# SolarSimulatorPanel.net
KiCad netlist of a schematic drawn in EAGLE
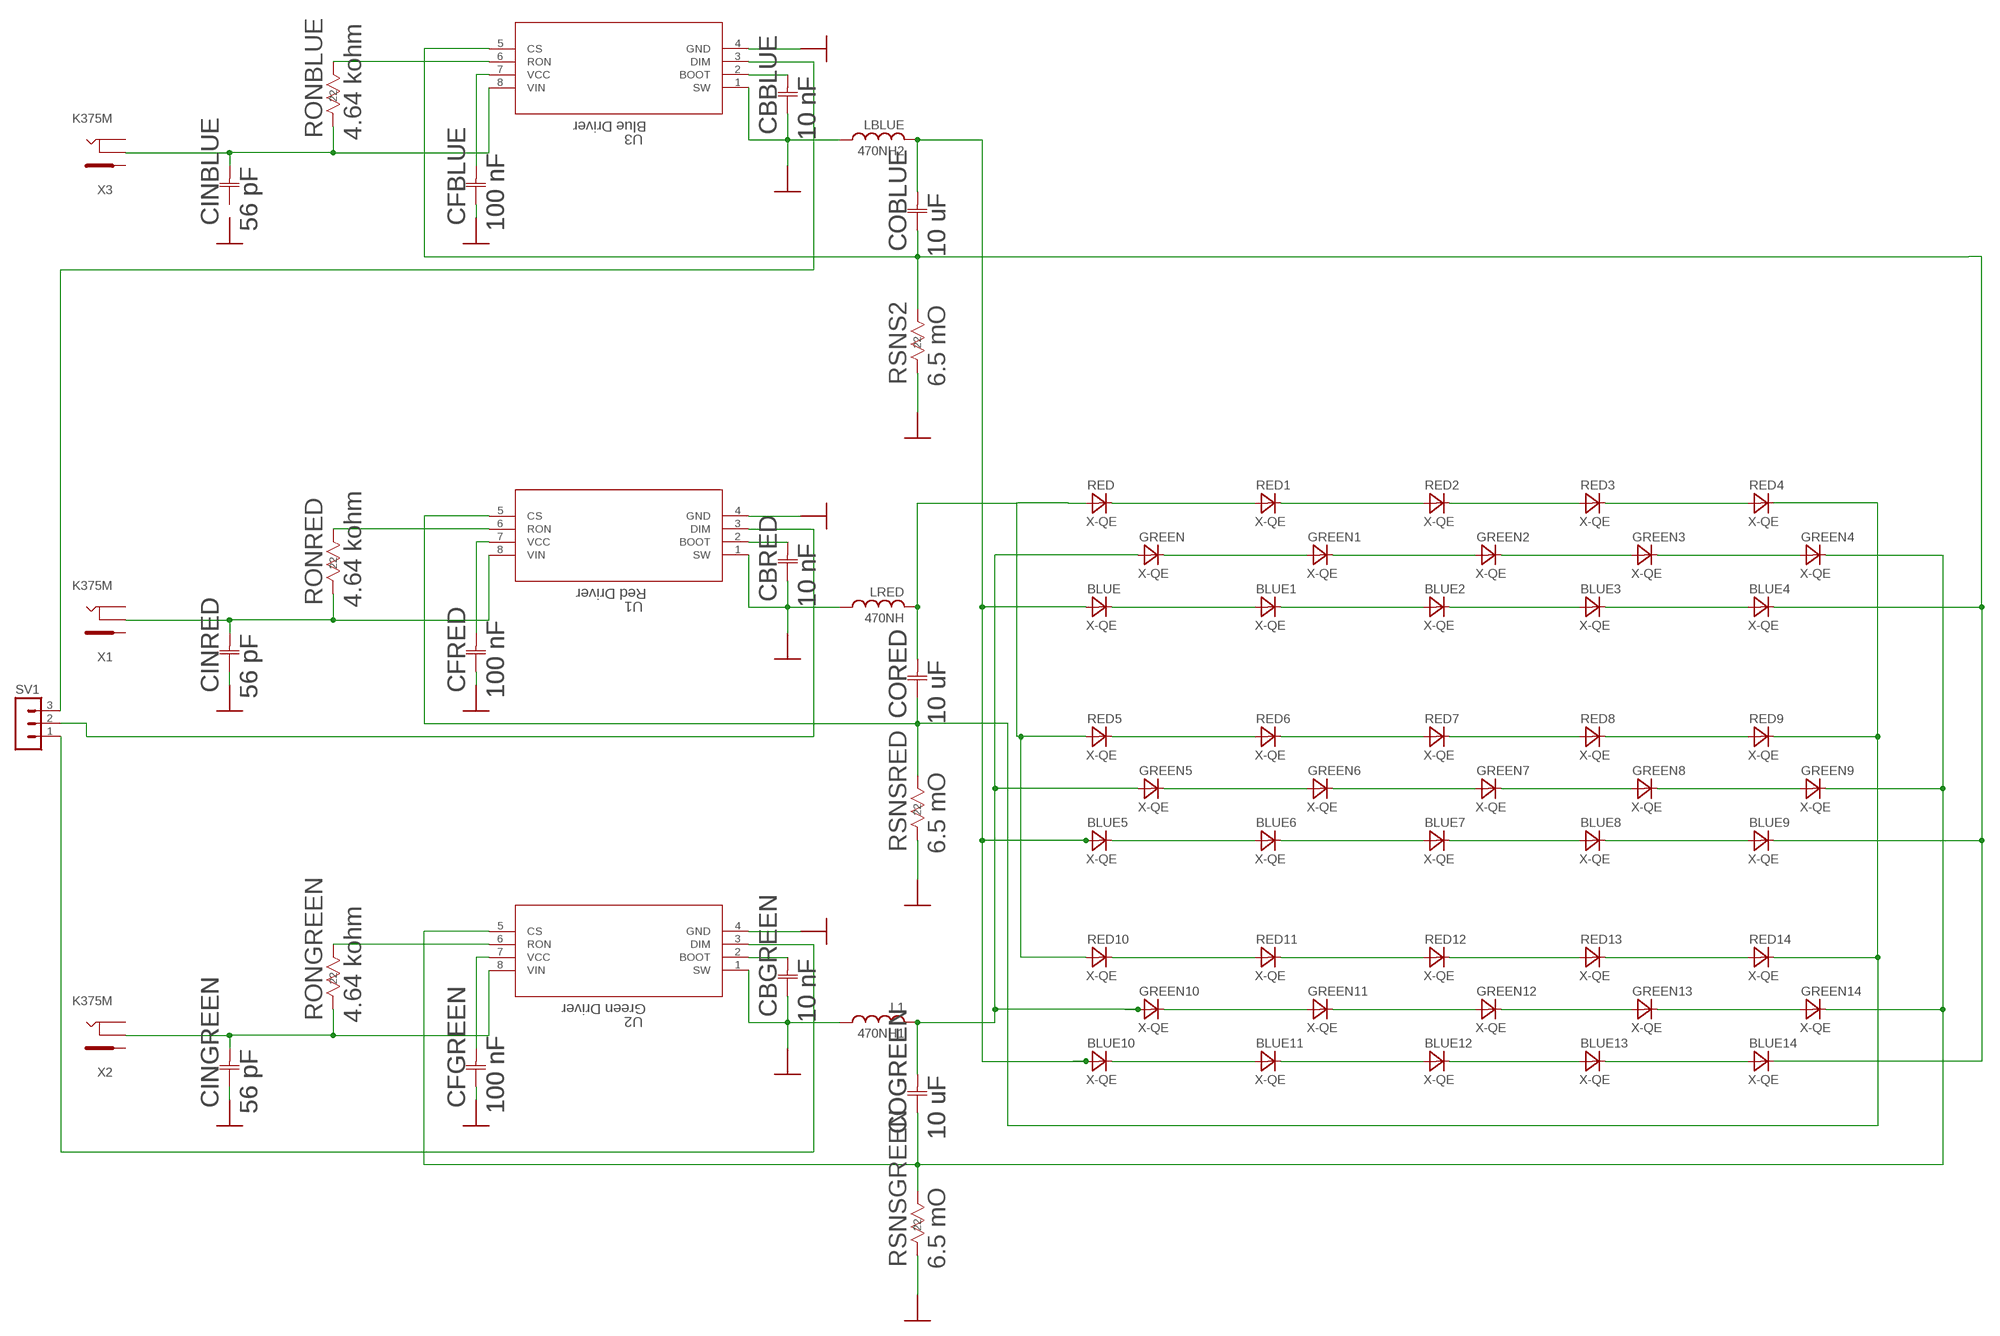
[diagram p0: schematic, sheet 1]

(export (version "E")
  (design (tool "Eeschema 10.0.6"))
  (components
    (comp (ref "470NH")
      (value "LRED")
      (footprint "eagle-import:CAPC2012X135N")
      (libsource (lib "eagle-import") (part "LQM21INDUCTOR"))
    )
    (comp (ref "470NH1")
      (value "L1")
      (footprint "eagle-import:CAPC2012X135N")
      (libsource (lib "eagle-import") (part "LQM21INDUCTOR"))
    )
    (comp (ref "470NH2")
      (value "LBLUE")
      (footprint "eagle-import:CAPC2012X135N")
      (libsource (lib "eagle-import") (part "LQM21INDUCTOR"))
    )
    (comp (ref "BLUE")
      (value "X-QE")
      (footprint "eagle-import:X-QE")
      (libsource (lib "eagle-import") (part "X-QE"))
    )
    (comp (ref "BLUE1")
      (value "X-QE")
      (footprint "eagle-import:X-QE")
      (libsource (lib "eagle-import") (part "X-QE"))
    )
    (comp (ref "BLUE2")
      (value "X-QE")
      (footprint "eagle-import:X-QE")
      (libsource (lib "eagle-import") (part "X-QE"))
    )
    (comp (ref "BLUE3")
      (value "X-QE")
      (footprint "eagle-import:X-QE")
      (libsource (lib "eagle-import") (part "X-QE"))
    )
    (comp (ref "BLUE4")
      (value "X-QE")
      (footprint "eagle-import:X-QE")
      (libsource (lib "eagle-import") (part "X-QE"))
    )
    (comp (ref "BLUE5")
      (value "X-QE")
      (footprint "eagle-import:X-QE")
      (libsource (lib "eagle-import") (part "X-QE"))
    )
    (comp (ref "BLUE6")
      (value "X-QE")
      (footprint "eagle-import:X-QE")
      (libsource (lib "eagle-import") (part "X-QE"))
    )
    (comp (ref "BLUE7")
      (value "X-QE")
      (footprint "eagle-import:X-QE")
      (libsource (lib "eagle-import") (part "X-QE"))
    )
    (comp (ref "BLUE8")
      (value "X-QE")
      (footprint "eagle-import:X-QE")
      (libsource (lib "eagle-import") (part "X-QE"))
    )
    (comp (ref "BLUE9")
      (value "X-QE")
      (footprint "eagle-import:X-QE")
      (libsource (lib "eagle-import") (part "X-QE"))
    )
    (comp (ref "BLUE10")
      (value "X-QE")
      (footprint "eagle-import:X-QE")
      (libsource (lib "eagle-import") (part "X-QE"))
    )
    (comp (ref "BLUE11")
      (value "X-QE")
      (footprint "eagle-import:X-QE")
      (libsource (lib "eagle-import") (part "X-QE"))
    )
    (comp (ref "BLUE12")
      (value "X-QE")
      (footprint "eagle-import:X-QE")
      (libsource (lib "eagle-import") (part "X-QE"))
    )
    (comp (ref "BLUE13")
      (value "X-QE")
      (footprint "eagle-import:X-QE")
      (libsource (lib "eagle-import") (part "X-QE"))
    )
    (comp (ref "BLUE14")
      (value "X-QE")
      (footprint "eagle-import:X-QE")
      (libsource (lib "eagle-import") (part "X-QE"))
    )
    (comp (ref "CBBLUE")
      (value "10 nF")
      (footprint "eagle-import:C1206K")
      (libsource (lib "eagle-import") (part "CB"))
    )
    (comp (ref "CBGREEN")
      (value "10 nF")
      (footprint "eagle-import:C1206K")
      (libsource (lib "eagle-import") (part "CB"))
    )
    (comp (ref "CBRED")
      (value "10 nF")
      (footprint "eagle-import:C1206K")
      (libsource (lib "eagle-import") (part "CB"))
    )
    (comp (ref "CFBLUE")
      (value "100 nF")
      (footprint "eagle-import:C1206")
      (libsource (lib "eagle-import") (part "CFCF"))
    )
    (comp (ref "CFGREEN")
      (value "100 nF")
      (footprint "eagle-import:C1206")
      (libsource (lib "eagle-import") (part "CFCF"))
    )
    (comp (ref "CFRED")
      (value "100 nF")
      (footprint "eagle-import:C1206")
      (libsource (lib "eagle-import") (part "CFCF"))
    )
    (comp (ref "CINBLUE")
      (value "56 pF")
      (footprint "eagle-import:CAP_0603G")
      (fields (field (name "MANUFACTURER_PART_NUMBER") "06031A560GAT2A"))
      (libsource (lib "eagle-import") (part "INPUTCAPACITOR"))
    )
    (comp (ref "CINGREEN")
      (value "56 pF")
      (footprint "eagle-import:CAP_0603G")
      (fields (field (name "MANUFACTURER_PART_NUMBER") "06031A560GAT2A"))
      (libsource (lib "eagle-import") (part "INPUTCAPACITOR"))
    )
    (comp (ref "CINRED")
      (value "56 pF")
      (footprint "eagle-import:CAP_0603G")
      (fields (field (name "MANUFACTURER_PART_NUMBER") "06031A560GAT2A"))
      (libsource (lib "eagle-import") (part "INPUTCAPACITOR"))
    )
    (comp (ref "COBLUE")
      (value "10 uF")
      (footprint "eagle-import:CAP_3225")
      (fields (field (name "MANUFACTURER_PART_NUMBER") "C3225X7R1H106M250AC"))
      (libsource (lib "eagle-import") (part "OUTPUTCAPACITOR"))
    )
    (comp (ref "COGREEN")
      (value "10 uF")
      (footprint "eagle-import:CAP_3225")
      (fields (field (name "MANUFACTURER_PART_NUMBER") "C3225X7R1H106M250AC"))
      (libsource (lib "eagle-import") (part "OUTPUTCAPACITOR"))
    )
    (comp (ref "CORED")
      (value "10 uF")
      (footprint "eagle-import:CAP_3225")
      (fields (field (name "MANUFACTURER_PART_NUMBER") "C3225X7R1H106M250AC"))
      (libsource (lib "eagle-import") (part "OUTPUTCAPACITOR"))
    )
    (comp (ref "GREEN")
      (value "X-QE")
      (footprint "eagle-import:X-QE")
      (libsource (lib "eagle-import") (part "X-QE"))
    )
    (comp (ref "GREEN1")
      (value "X-QE")
      (footprint "eagle-import:X-QE")
      (libsource (lib "eagle-import") (part "X-QE"))
    )
    (comp (ref "GREEN2")
      (value "X-QE")
      (footprint "eagle-import:X-QE")
      (libsource (lib "eagle-import") (part "X-QE"))
    )
    (comp (ref "GREEN3")
      (value "X-QE")
      (footprint "eagle-import:X-QE")
      (libsource (lib "eagle-import") (part "X-QE"))
    )
    (comp (ref "GREEN4")
      (value "X-QE")
      (footprint "eagle-import:X-QE")
      (libsource (lib "eagle-import") (part "X-QE"))
    )
    (comp (ref "GREEN5")
      (value "X-QE")
      (footprint "eagle-import:X-QE")
      (libsource (lib "eagle-import") (part "X-QE"))
    )
    (comp (ref "GREEN6")
      (value "X-QE")
      (footprint "eagle-import:X-QE")
      (libsource (lib "eagle-import") (part "X-QE"))
    )
    (comp (ref "GREEN7")
      (value "X-QE")
      (footprint "eagle-import:X-QE")
      (libsource (lib "eagle-import") (part "X-QE"))
    )
    (comp (ref "GREEN8")
      (value "X-QE")
      (footprint "eagle-import:X-QE")
      (libsource (lib "eagle-import") (part "X-QE"))
    )
    (comp (ref "GREEN9")
      (value "X-QE")
      (footprint "eagle-import:X-QE")
      (libsource (lib "eagle-import") (part "X-QE"))
    )
    (comp (ref "GREEN10")
      (value "X-QE")
      (footprint "eagle-import:X-QE")
      (libsource (lib "eagle-import") (part "X-QE"))
    )
    (comp (ref "GREEN11")
      (value "X-QE")
      (footprint "eagle-import:X-QE")
      (libsource (lib "eagle-import") (part "X-QE"))
    )
    (comp (ref "GREEN12")
      (value "X-QE")
      (footprint "eagle-import:X-QE")
      (libsource (lib "eagle-import") (part "X-QE"))
    )
    (comp (ref "GREEN13")
      (value "X-QE")
      (footprint "eagle-import:X-QE")
      (libsource (lib "eagle-import") (part "X-QE"))
    )
    (comp (ref "GREEN14")
      (value "X-QE")
      (footprint "eagle-import:X-QE")
      (libsource (lib "eagle-import") (part "X-QE"))
    )
    (comp (ref "RED")
      (value "X-QE")
      (footprint "eagle-import:X-QE")
      (libsource (lib "eagle-import") (part "X-QE"))
    )
    (comp (ref "RED1")
      (value "X-QE")
      (footprint "eagle-import:X-QE")
      (libsource (lib "eagle-import") (part "X-QE"))
    )
    (comp (ref "RED2")
      (value "X-QE")
      (footprint "eagle-import:X-QE")
      (libsource (lib "eagle-import") (part "X-QE"))
    )
    (comp (ref "RED3")
      (value "X-QE")
      (footprint "eagle-import:X-QE")
      (libsource (lib "eagle-import") (part "X-QE"))
    )
    (comp (ref "RED4")
      (value "X-QE")
      (footprint "eagle-import:X-QE")
      (libsource (lib "eagle-import") (part "X-QE"))
    )
    (comp (ref "RED5")
      (value "X-QE")
      (footprint "eagle-import:X-QE")
      (libsource (lib "eagle-import") (part "X-QE"))
    )
    (comp (ref "RED6")
      (value "X-QE")
      (footprint "eagle-import:X-QE")
      (libsource (lib "eagle-import") (part "X-QE"))
    )
    (comp (ref "RED7")
      (value "X-QE")
      (footprint "eagle-import:X-QE")
      (libsource (lib "eagle-import") (part "X-QE"))
    )
    (comp (ref "RED8")
      (value "X-QE")
      (footprint "eagle-import:X-QE")
      (libsource (lib "eagle-import") (part "X-QE"))
    )
    (comp (ref "RED9")
      (value "X-QE")
      (footprint "eagle-import:X-QE")
      (libsource (lib "eagle-import") (part "X-QE"))
    )
    (comp (ref "RED10")
      (value "X-QE")
      (footprint "eagle-import:X-QE")
      (libsource (lib "eagle-import") (part "X-QE"))
    )
    (comp (ref "RED11")
      (value "X-QE")
      (footprint "eagle-import:X-QE")
      (libsource (lib "eagle-import") (part "X-QE"))
    )
    (comp (ref "RED12")
      (value "X-QE")
      (footprint "eagle-import:X-QE")
      (libsource (lib "eagle-import") (part "X-QE"))
    )
    (comp (ref "RED13")
      (value "X-QE")
      (footprint "eagle-import:X-QE")
      (libsource (lib "eagle-import") (part "X-QE"))
    )
    (comp (ref "RED14")
      (value "X-QE")
      (footprint "eagle-import:X-QE")
      (libsource (lib "eagle-import") (part "X-QE"))
    )
    (comp (ref "RONBLUE")
      (value "4.64 kohm")
      (footprint "eagle-import:RC0603N")
      (fields (field (name "MANUFACTURER_PART_NUMBER") "RT0603BRD074K64L"))
      (libsource (lib "eagle-import") (part "RT0603BRD074K64L"))
    )
    (comp (ref "RONGREEN")
      (value "4.64 kohm")
      (footprint "eagle-import:RC0603N")
      (fields (field (name "MANUFACTURER_PART_NUMBER") "RT0603BRD074K64L"))
      (libsource (lib "eagle-import") (part "RT0603BRD074K64L"))
    )
    (comp (ref "RONRED")
      (value "4.64 kohm")
      (footprint "eagle-import:RC0603N")
      (fields (field (name "MANUFACTURER_PART_NUMBER") "RT0603BRD074K64L"))
      (libsource (lib "eagle-import") (part "RT0603BRD074K64L"))
    )
    (comp (ref "RSNS2")
      (value "6.5 mO")
      (footprint "eagle-import:R2512")
      (libsource (lib "eagle-import") (part "RSNS"))
    )
    (comp (ref "RSNSGREEN")
      (value "6.5 mO")
      (footprint "eagle-import:R2512")
      (libsource (lib "eagle-import") (part "RSNS"))
    )
    (comp (ref "RSNSRED")
      (value "6.5 mO")
      (footprint "eagle-import:R2512")
      (libsource (lib "eagle-import") (part "RSNS"))
    )
    (comp (ref "SV1")
      (value "MA03-1")
      (footprint "eagle-import:MA03-1")
      (libsource (lib "eagle-import") (part "MA03-1"))
    )
    (comp (ref "U1")
      (value "Red Driver")
      (footprint "eagle-import:M08A")
      (fields (field (name "MANUFACTURER_PART_NUMBER") "lm3404hvma"))
      (libsource (lib "eagle-import") (part "LM3404HVMA"))
    )
    (comp (ref "U2")
      (value "Green Driver")
      (footprint "eagle-import:M08A")
      (fields (field (name "MANUFACTURER_PART_NUMBER") "lm3404hvma"))
      (libsource (lib "eagle-import") (part "LM3404HVMA"))
    )
    (comp (ref "U3")
      (value "Blue Driver")
      (footprint "eagle-import:M08A")
      (fields (field (name "MANUFACTURER_PART_NUMBER") "lm3404hvma"))
      (libsource (lib "eagle-import") (part "LM3404HVMA"))
    )
    (comp (ref "X1")
      (value "K375M")
      (footprint "eagle-import:K375M")
      (libsource (lib "eagle-import") (part "K375M"))
    )
    (comp (ref "X2")
      (value "K375M")
      (footprint "eagle-import:K375M")
      (libsource (lib "eagle-import") (part "K375M"))
    )
    (comp (ref "X3")
      (value "K375M")
      (footprint "eagle-import:K375M")
      (libsource (lib "eagle-import") (part "K375M"))
    )
  )
  (nets
    (net (code "1") (name "Net-(BLUE-A)") (class "Default")
      (node (ref "470NH2") (pin "2") (pinfunction "2_2") (pintype "passive"))
      (node (ref "BLUE") (pin "INPUT") (pinfunction "A_INPUT") (pintype "passive"))
      (node (ref "BLUE10") (pin "INPUT") (pinfunction "A_INPUT") (pintype "passive"))
      (node (ref "BLUE5") (pin "INPUT") (pinfunction "A_INPUT") (pintype "passive"))
      (node (ref "COBLUE") (pin "2") (pinfunction "22_2") (pintype "passive"))
    )
    (net (code "2") (name "Net-(BLUE-C)") (class "Default")
      (node (ref "BLUE") (pin "OUTPUT") (pinfunction "C_OUTPUT") (pintype "passive"))
      (node (ref "BLUE1") (pin "INPUT") (pinfunction "A_INPUT") (pintype "passive"))
    )
    (net (code "3") (name "Net-(BLUE1-C)") (class "Default")
      (node (ref "BLUE1") (pin "OUTPUT") (pinfunction "C_OUTPUT") (pintype "passive"))
      (node (ref "BLUE2") (pin "INPUT") (pinfunction "A_INPUT") (pintype "passive"))
    )
    (net (code "4") (name "Net-(BLUE2-C)") (class "Default")
      (node (ref "BLUE2") (pin "OUTPUT") (pinfunction "C_OUTPUT") (pintype "passive"))
      (node (ref "BLUE3") (pin "INPUT") (pinfunction "A_INPUT") (pintype "passive"))
    )
    (net (code "5") (name "Net-(BLUE3-C)") (class "Default")
      (node (ref "BLUE3") (pin "OUTPUT") (pinfunction "C_OUTPUT") (pintype "passive"))
      (node (ref "BLUE4") (pin "INPUT") (pinfunction "A_INPUT") (pintype "passive"))
    )
    (net (code "6") (name "Net-(BLUE5-C)") (class "Default")
      (node (ref "BLUE5") (pin "OUTPUT") (pinfunction "C_OUTPUT") (pintype "passive"))
      (node (ref "BLUE6") (pin "INPUT") (pinfunction "A_INPUT") (pintype "passive"))
    )
    (net (code "7") (name "Net-(BLUE6-C)") (class "Default")
      (node (ref "BLUE6") (pin "OUTPUT") (pinfunction "C_OUTPUT") (pintype "passive"))
      (node (ref "BLUE7") (pin "INPUT") (pinfunction "A_INPUT") (pintype "passive"))
    )
    (net (code "8") (name "Net-(BLUE7-C)") (class "Default")
      (node (ref "BLUE7") (pin "OUTPUT") (pinfunction "C_OUTPUT") (pintype "passive"))
      (node (ref "BLUE8") (pin "INPUT") (pinfunction "A_INPUT") (pintype "passive"))
    )
    (net (code "9") (name "Net-(BLUE8-C)") (class "Default")
      (node (ref "BLUE8") (pin "OUTPUT") (pinfunction "C_OUTPUT") (pintype "passive"))
      (node (ref "BLUE9") (pin "INPUT") (pinfunction "A_INPUT") (pintype "passive"))
    )
    (net (code "10") (name "Net-(BLUE10-C)") (class "Default")
      (node (ref "BLUE10") (pin "OUTPUT") (pinfunction "C_OUTPUT") (pintype "passive"))
      (node (ref "BLUE11") (pin "INPUT") (pinfunction "A_INPUT") (pintype "passive"))
    )
    (net (code "11") (name "Net-(BLUE11-C)") (class "Default")
      (node (ref "BLUE11") (pin "OUTPUT") (pinfunction "C_OUTPUT") (pintype "passive"))
      (node (ref "BLUE12") (pin "INPUT") (pinfunction "A_INPUT") (pintype "passive"))
    )
    (net (code "12") (name "Net-(BLUE12-C)") (class "Default")
      (node (ref "BLUE12") (pin "OUTPUT") (pinfunction "C_OUTPUT") (pintype "passive"))
      (node (ref "BLUE13") (pin "INPUT") (pinfunction "A_INPUT") (pintype "passive"))
    )
    (net (code "13") (name "Net-(BLUE13-C)") (class "Default")
      (node (ref "BLUE13") (pin "OUTPUT") (pinfunction "C_OUTPUT") (pintype "passive"))
      (node (ref "BLUE14") (pin "INPUT") (pinfunction "A_INPUT") (pintype "passive"))
    )
    (net (code "14") (name "Net-(BLUE14-C)") (class "Default")
      (node (ref "BLUE14") (pin "OUTPUT") (pinfunction "C_OUTPUT") (pintype "passive"))
      (node (ref "BLUE4") (pin "OUTPUT") (pinfunction "C_OUTPUT") (pintype "passive"))
      (node (ref "BLUE9") (pin "OUTPUT") (pinfunction "C_OUTPUT") (pintype "passive"))
      (node (ref "COBLUE") (pin "1") (pinfunction "11_1") (pintype "passive"))
      (node (ref "RSNS2") (pin "1") (pinfunction "11_1") (pintype "passive"))
      (node (ref "U3") (pin "5") (pinfunction "CS_5") (pintype "input"))
    )
    (net (code "15") (name "Net-(CBBLUE-11)") (class "Default")
      (node (ref "470NH2") (pin "1") (pinfunction "1_1") (pintype "passive"))
      (node (ref "CBBLUE") (pin "1") (pinfunction "11_1") (pintype "passive"))
      (node (ref "U3") (pin "1") (pinfunction "SW_1") (pintype "power_in"))
    )
    (net (code "16") (name "Net-(CBBLUE-22)") (class "Default")
      (node (ref "CBBLUE") (pin "2") (pinfunction "22_2") (pintype "passive"))
      (node (ref "U3") (pin "2") (pinfunction "BOOT_2") (pintype "input"))
    )
    (net (code "17") (name "Net-(CBGREEN-11)") (class "Default")
      (node (ref "470NH1") (pin "1") (pinfunction "1_1") (pintype "passive"))
      (node (ref "CBGREEN") (pin "1") (pinfunction "11_1") (pintype "passive"))
      (node (ref "U2") (pin "1") (pinfunction "SW_1") (pintype "power_in"))
    )
    (net (code "18") (name "Net-(CBGREEN-22)") (class "Default")
      (node (ref "CBGREEN") (pin "2") (pinfunction "22_2") (pintype "passive"))
      (node (ref "U2") (pin "2") (pinfunction "BOOT_2") (pintype "input"))
    )
    (net (code "19") (name "Net-(CBRED-11)") (class "Default")
      (node (ref "470NH") (pin "1") (pinfunction "1_1") (pintype "passive"))
      (node (ref "CBRED") (pin "1") (pinfunction "11_1") (pintype "passive"))
      (node (ref "U1") (pin "1") (pinfunction "SW_1") (pintype "power_in"))
    )
    (net (code "20") (name "Net-(CBRED-22)") (class "Default")
      (node (ref "CBRED") (pin "2") (pinfunction "22_2") (pintype "passive"))
      (node (ref "U1") (pin "2") (pinfunction "BOOT_2") (pintype "input"))
    )
    (net (code "21") (name "Net-(CFBLUE-22)") (class "Default")
      (node (ref "CFBLUE") (pin "2") (pinfunction "22_2") (pintype "passive"))
      (node (ref "U3") (pin "7") (pinfunction "VCC_7") (pintype "power_in"))
    )
    (net (code "22") (name "Net-(CFGREEN-22)") (class "Default")
      (node (ref "CFGREEN") (pin "2") (pinfunction "22_2") (pintype "passive"))
      (node (ref "U2") (pin "7") (pinfunction "VCC_7") (pintype "power_in"))
    )
    (net (code "23") (name "Net-(CFRED-22)") (class "Default")
      (node (ref "CFRED") (pin "2") (pinfunction "22_2") (pintype "passive"))
      (node (ref "U1") (pin "7") (pinfunction "VCC_7") (pintype "power_in"))
    )
    (net (code "24") (name "Net-(CINBLUE-22)") (class "Default")
      (node (ref "CINBLUE") (pin "2") (pinfunction "22_2") (pintype "passive"))
      (node (ref "RONBLUE") (pin "2") (pinfunction "22_2") (pintype "passive"))
      (node (ref "U3") (pin "8") (pinfunction "VIN_8") (pintype "power_in"))
      (node (ref "X3") (pin "3") (pinfunction "3_3") (pintype "passive"))
    )
    (net (code "25") (name "Net-(CINGREEN-22)") (class "Default")
      (node (ref "CINGREEN") (pin "2") (pinfunction "22_2") (pintype "passive"))
      (node (ref "RONGREEN") (pin "2") (pinfunction "22_2") (pintype "passive"))
      (node (ref "U2") (pin "8") (pinfunction "VIN_8") (pintype "power_in"))
      (node (ref "X2") (pin "3") (pinfunction "3_3") (pintype "passive"))
    )
    (net (code "26") (name "Net-(CINRED-22)") (class "Default")
      (node (ref "CINRED") (pin "2") (pinfunction "22_2") (pintype "passive"))
      (node (ref "RONRED") (pin "2") (pinfunction "22_2") (pintype "passive"))
      (node (ref "U1") (pin "8") (pinfunction "VIN_8") (pintype "power_in"))
      (node (ref "X1") (pin "3") (pinfunction "3_3") (pintype "passive"))
    )
    (net (code "27") (name "Net-(COGREEN-11)") (class "Default")
      (node (ref "COGREEN") (pin "1") (pinfunction "11_1") (pintype "passive"))
      (node (ref "GREEN14") (pin "OUTPUT") (pinfunction "C_OUTPUT") (pintype "passive"))
      (node (ref "GREEN4") (pin "OUTPUT") (pinfunction "C_OUTPUT") (pintype "passive"))
      (node (ref "GREEN9") (pin "OUTPUT") (pinfunction "C_OUTPUT") (pintype "passive"))
      (node (ref "RSNSGREEN") (pin "1") (pinfunction "11_1") (pintype "passive"))
      (node (ref "U2") (pin "5") (pinfunction "CS_5") (pintype "input"))
    )
    (net (code "28") (name "Net-(COGREEN-22)") (class "Default")
      (node (ref "470NH1") (pin "2") (pinfunction "2_2") (pintype "passive"))
      (node (ref "COGREEN") (pin "2") (pinfunction "22_2") (pintype "passive"))
      (node (ref "GREEN") (pin "INPUT") (pinfunction "A_INPUT") (pintype "passive"))
      (node (ref "GREEN10") (pin "INPUT") (pinfunction "A_INPUT") (pintype "passive"))
    )
    (net (code "29") (name "Net-(CORED-11)") (class "Default")
      (node (ref "CORED") (pin "1") (pinfunction "11_1") (pintype "passive"))
      (node (ref "RED14") (pin "OUTPUT") (pinfunction "C_OUTPUT") (pintype "passive"))
      (node (ref "RED4") (pin "OUTPUT") (pinfunction "C_OUTPUT") (pintype "passive"))
      (node (ref "RED9") (pin "OUTPUT") (pinfunction "C_OUTPUT") (pintype "passive"))
      (node (ref "RSNSRED") (pin "1") (pinfunction "11_1") (pintype "passive"))
      (node (ref "U1") (pin "5") (pinfunction "CS_5") (pintype "input"))
    )
    (net (code "30") (name "Net-(CORED-22)") (class "Default")
      (node (ref "470NH") (pin "2") (pinfunction "2_2") (pintype "passive"))
      (node (ref "CORED") (pin "2") (pinfunction "22_2") (pintype "passive"))
      (node (ref "RED") (pin "INPUT") (pinfunction "A_INPUT") (pintype "passive"))
      (node (ref "RED10") (pin "INPUT") (pinfunction "A_INPUT") (pintype "passive"))
      (node (ref "RED5") (pin "INPUT") (pinfunction "A_INPUT") (pintype "passive"))
    )
    (net (code "31") (name "Net-(GREEN-C)") (class "Default")
      (node (ref "GREEN") (pin "OUTPUT") (pinfunction "C_OUTPUT") (pintype "passive"))
      (node (ref "GREEN1") (pin "INPUT") (pinfunction "A_INPUT") (pintype "passive"))
    )
    (net (code "32") (name "Net-(GREEN1-C)") (class "Default")
      (node (ref "GREEN1") (pin "OUTPUT") (pinfunction "C_OUTPUT") (pintype "passive"))
      (node (ref "GREEN2") (pin "INPUT") (pinfunction "A_INPUT") (pintype "passive"))
    )
    (net (code "33") (name "Net-(GREEN2-C)") (class "Default")
      (node (ref "GREEN2") (pin "OUTPUT") (pinfunction "C_OUTPUT") (pintype "passive"))
      (node (ref "GREEN3") (pin "INPUT") (pinfunction "A_INPUT") (pintype "passive"))
    )
    (net (code "34") (name "Net-(GREEN3-C)") (class "Default")
      (node (ref "GREEN3") (pin "OUTPUT") (pinfunction "C_OUTPUT") (pintype "passive"))
      (node (ref "GREEN4") (pin "INPUT") (pinfunction "A_INPUT") (pintype "passive"))
    )
    (net (code "35") (name "Net-(GREEN5-C)") (class "Default")
      (node (ref "GREEN5") (pin "OUTPUT") (pinfunction "C_OUTPUT") (pintype "passive"))
      (node (ref "GREEN6") (pin "INPUT") (pinfunction "A_INPUT") (pintype "passive"))
    )
    (net (code "36") (name "Net-(GREEN6-C)") (class "Default")
      (node (ref "GREEN6") (pin "OUTPUT") (pinfunction "C_OUTPUT") (pintype "passive"))
      (node (ref "GREEN7") (pin "INPUT") (pinfunction "A_INPUT") (pintype "passive"))
    )
    (net (code "37") (name "Net-(GREEN7-C)") (class "Default")
      (node (ref "GREEN7") (pin "OUTPUT") (pinfunction "C_OUTPUT") (pintype "passive"))
      (node (ref "GREEN8") (pin "INPUT") (pinfunction "A_INPUT") (pintype "passive"))
    )
    (net (code "38") (name "Net-(GREEN8-C)") (class "Default")
      (node (ref "GREEN8") (pin "OUTPUT") (pinfunction "C_OUTPUT") (pintype "passive"))
      (node (ref "GREEN9") (pin "INPUT") (pinfunction "A_INPUT") (pintype "passive"))
    )
    (net (code "39") (name "Net-(GREEN10-C)") (class "Default")
      (node (ref "GREEN10") (pin "OUTPUT") (pinfunction "C_OUTPUT") (pintype "passive"))
      (node (ref "GREEN11") (pin "INPUT") (pinfunction "A_INPUT") (pintype "passive"))
    )
    (net (code "40") (name "Net-(GREEN11-C)") (class "Default")
      (node (ref "GREEN11") (pin "OUTPUT") (pinfunction "C_OUTPUT") (pintype "passive"))
      (node (ref "GREEN12") (pin "INPUT") (pinfunction "A_INPUT") (pintype "passive"))
    )
    (net (code "41") (name "Net-(GREEN12-C)") (class "Default")
      (node (ref "GREEN12") (pin "OUTPUT") (pinfunction "C_OUTPUT") (pintype "passive"))
      (node (ref "GREEN13") (pin "INPUT") (pinfunction "A_INPUT") (pintype "passive"))
    )
    (net (code "42") (name "Net-(GREEN13-C)") (class "Default")
      (node (ref "GREEN13") (pin "OUTPUT") (pinfunction "C_OUTPUT") (pintype "passive"))
      (node (ref "GREEN14") (pin "INPUT") (pinfunction "A_INPUT") (pintype "passive"))
    )
    (net (code "43") (name "Net-(RED-C)") (class "Default")
      (node (ref "RED") (pin "OUTPUT") (pinfunction "C_OUTPUT") (pintype "passive"))
      (node (ref "RED1") (pin "INPUT") (pinfunction "A_INPUT") (pintype "passive"))
    )
    (net (code "44") (name "Net-(RED1-C)") (class "Default")
      (node (ref "RED1") (pin "OUTPUT") (pinfunction "C_OUTPUT") (pintype "passive"))
      (node (ref "RED2") (pin "INPUT") (pinfunction "A_INPUT") (pintype "passive"))
    )
    (net (code "45") (name "Net-(RED2-C)") (class "Default")
      (node (ref "RED2") (pin "OUTPUT") (pinfunction "C_OUTPUT") (pintype "passive"))
      (node (ref "RED3") (pin "INPUT") (pinfunction "A_INPUT") (pintype "passive"))
    )
    (net (code "46") (name "Net-(RED3-C)") (class "Default")
      (node (ref "RED3") (pin "OUTPUT") (pinfunction "C_OUTPUT") (pintype "passive"))
      (node (ref "RED4") (pin "INPUT") (pinfunction "A_INPUT") (pintype "passive"))
    )
    (net (code "47") (name "Net-(RED5-C)") (class "Default")
      (node (ref "RED5") (pin "OUTPUT") (pinfunction "C_OUTPUT") (pintype "passive"))
      (node (ref "RED6") (pin "INPUT") (pinfunction "A_INPUT") (pintype "passive"))
    )
    (net (code "48") (name "Net-(RED6-C)") (class "Default")
      (node (ref "RED6") (pin "OUTPUT") (pinfunction "C_OUTPUT") (pintype "passive"))
      (node (ref "RED7") (pin "INPUT") (pinfunction "A_INPUT") (pintype "passive"))
    )
    (net (code "49") (name "Net-(RED7-C)") (class "Default")
      (node (ref "RED7") (pin "OUTPUT") (pinfunction "C_OUTPUT") (pintype "passive"))
      (node (ref "RED8") (pin "INPUT") (pinfunction "A_INPUT") (pintype "passive"))
    )
    (net (code "50") (name "Net-(RED8-C)") (class "Default")
      (node (ref "RED8") (pin "OUTPUT") (pinfunction "C_OUTPUT") (pintype "passive"))
      (node (ref "RED9") (pin "INPUT") (pinfunction "A_INPUT") (pintype "passive"))
    )
    (net (code "51") (name "Net-(RED10-C)") (class "Default")
      (node (ref "RED10") (pin "OUTPUT") (pinfunction "C_OUTPUT") (pintype "passive"))
      (node (ref "RED11") (pin "INPUT") (pinfunction "A_INPUT") (pintype "passive"))
    )
    (net (code "52") (name "Net-(RED11-C)") (class "Default")
      (node (ref "RED11") (pin "OUTPUT") (pinfunction "C_OUTPUT") (pintype "passive"))
      (node (ref "RED12") (pin "INPUT") (pinfunction "A_INPUT") (pintype "passive"))
    )
    (net (code "53") (name "Net-(RED12-C)") (class "Default")
      (node (ref "RED12") (pin "OUTPUT") (pinfunction "C_OUTPUT") (pintype "passive"))
      (node (ref "RED13") (pin "INPUT") (pinfunction "A_INPUT") (pintype "passive"))
    )
    (net (code "54") (name "Net-(RED13-C)") (class "Default")
      (node (ref "RED13") (pin "OUTPUT") (pinfunction "C_OUTPUT") (pintype "passive"))
      (node (ref "RED14") (pin "INPUT") (pinfunction "A_INPUT") (pintype "passive"))
    )
    (net (code "55") (name "Net-(RONBLUE-11)") (class "Default")
      (node (ref "RONBLUE") (pin "1") (pinfunction "11_1") (pintype "passive"))
      (node (ref "U3") (pin "6") (pinfunction "RON_6") (pintype "input"))
    )
    (net (code "56") (name "Net-(RONGREEN-11)") (class "Default")
      (node (ref "RONGREEN") (pin "1") (pinfunction "11_1") (pintype "passive"))
      (node (ref "U2") (pin "6") (pinfunction "RON_6") (pintype "input"))
    )
    (net (code "57") (name "Net-(RONRED-11)") (class "Default")
      (node (ref "RONRED") (pin "1") (pinfunction "11_1") (pintype "passive"))
      (node (ref "U1") (pin "6") (pinfunction "RON_6") (pintype "input"))
    )
    (net (code "58") (name "Net-(U1-DIM)") (class "Default")
      (node (ref "SV1") (pin "2") (pinfunction "2_2") (pintype "passive"))
      (node (ref "U1") (pin "3") (pinfunction "DIM_3") (pintype "input"))
    )
    (net (code "59") (name "Net-(U2-DIM)") (class "Default")
      (node (ref "SV1") (pin "1") (pinfunction "1_1") (pintype "passive"))
      (node (ref "U2") (pin "3") (pinfunction "DIM_3") (pintype "input"))
    )
    (net (code "60") (name "Net-(U3-DIM)") (class "Default")
      (node (ref "SV1") (pin "3") (pinfunction "3_3") (pintype "passive"))
      (node (ref "U3") (pin "3") (pinfunction "DIM_3") (pintype "input"))
    )
    (net (code "61") (name "unconnected-(CFBLUE-11-Pad1)") (class "Default")
      (node (ref "CFBLUE") (pin "1") (pinfunction "11_1") (pintype "passive"))
    )
    (net (code "62") (name "unconnected-(CFGREEN-11-Pad1)") (class "Default")
      (node (ref "CFGREEN") (pin "1") (pinfunction "11_1") (pintype "passive"))
    )
    (net (code "63") (name "unconnected-(CFRED-11-Pad1)") (class "Default")
      (node (ref "CFRED") (pin "1") (pinfunction "11_1") (pintype "passive"))
    )
    (net (code "64") (name "unconnected-(CINBLUE-11-Pad1)") (class "Default")
      (node (ref "CINBLUE") (pin "1") (pinfunction "11_1") (pintype "passive"))
    )
    (net (code "65") (name "unconnected-(CINGREEN-11-Pad1)") (class "Default")
      (node (ref "CINGREEN") (pin "1") (pinfunction "11_1") (pintype "passive"))
    )
    (net (code "66") (name "unconnected-(CINRED-11-Pad1)") (class "Default")
      (node (ref "CINRED") (pin "1") (pinfunction "11_1") (pintype "passive"))
    )
    (net (code "67") (name "unconnected-(GREEN5-A-PadINPUT)") (class "Default")
      (node (ref "GREEN5") (pin "INPUT") (pinfunction "A_INPUT") (pintype "passive"))
    )
    (net (code "68") (name "unconnected-(RSNS2-22-Pad2)") (class "Default")
      (node (ref "RSNS2") (pin "2") (pinfunction "22_2") (pintype "passive"))
    )
    (net (code "69") (name "unconnected-(RSNSGREEN-22-Pad2)") (class "Default")
      (node (ref "RSNSGREEN") (pin "2") (pinfunction "22_2") (pintype "passive"))
    )
    (net (code "70") (name "unconnected-(RSNSRED-22-Pad2)") (class "Default")
      (node (ref "RSNSRED") (pin "2") (pinfunction "22_2") (pintype "passive"))
    )
    (net (code "71") (name "unconnected-(U1-GND-Pad4)") (class "Default")
      (node (ref "U1") (pin "4") (pinfunction "GND_4") (pintype "power_in"))
    )
    (net (code "72") (name "unconnected-(U2-GND-Pad4)") (class "Default")
      (node (ref "U2") (pin "4") (pinfunction "GND_4") (pintype "power_in"))
    )
    (net (code "73") (name "unconnected-(U3-GND-Pad4)") (class "Default")
      (node (ref "U3") (pin "4") (pinfunction "GND_4") (pintype "power_in"))
    )
    (net (code "74") (name "unconnected-(X1-Pad1)") (class "Default")
      (node (ref "X1") (pin "1") (pinfunction "1_1") (pintype "passive"))
    )
    (net (code "75") (name "unconnected-(X1-Pad2)") (class "Default")
      (node (ref "X1") (pin "2") (pinfunction "2_2") (pintype "passive"))
    )
    (net (code "76") (name "unconnected-(X2-Pad1)") (class "Default")
      (node (ref "X2") (pin "1") (pinfunction "1_1") (pintype "passive"))
    )
    (net (code "77") (name "unconnected-(X2-Pad2)") (class "Default")
      (node (ref "X2") (pin "2") (pinfunction "2_2") (pintype "passive"))
    )
    (net (code "78") (name "unconnected-(X3-Pad1)") (class "Default")
      (node (ref "X3") (pin "1") (pinfunction "1_1") (pintype "passive"))
    )
    (net (code "79") (name "unconnected-(X3-Pad2)") (class "Default")
      (node (ref "X3") (pin "2") (pinfunction "2_2") (pintype "passive"))
    )
  )
)
